# ppg.net
KiCad netlist of a schematic drawn in EAGLE
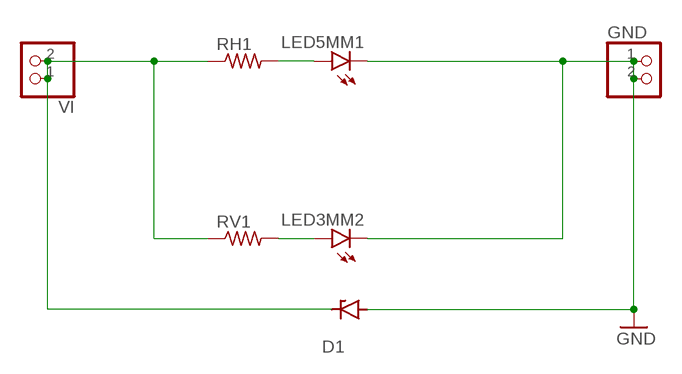
[diagram p0: schematic, sheet 1]

(export (version "E")
  (design (tool "Eeschema 10.0.6"))
  (components
    (comp (ref "D1")
      (value "ZENER-DIODEDO41Z10")
      (footprint "eagle-import:DO41Z10")
      (libsource (lib "eagle-import") (part "ZENER-DIODEDO41Z10"))
    )
    (comp (ref "GND")
      (value "PINHD-1X2")
      (footprint "eagle-import:1X02")
      (libsource (lib "eagle-import") (part "PINHD-1X2"))
    )
    (comp (ref "LED3MM2")
      (value "LED3MM")
      (footprint "eagle-import:LED3MM")
      (libsource (lib "eagle-import") (part "LED3MM"))
    )
    (comp (ref "LED5MM1")
      (value "LED5MM")
      (footprint "eagle-import:LED5MM")
      (libsource (lib "eagle-import") (part "LED5MM"))
    )
    (comp (ref "RH1")
      (value "R-US_VMTA55")
      (footprint "eagle-import:VMTA55")
      (libsource (lib "eagle-import") (part "R-US_VMTA55"))
    )
    (comp (ref "RV1")
      (value "R-US_0207/5V")
      (footprint "eagle-import:0207_5V")
      (libsource (lib "eagle-import") (part "R-US_0207/5V"))
    )
    (comp (ref "VI")
      (value "PINHD-1X2")
      (footprint "eagle-import:1X02")
      (libsource (lib "eagle-import") (part "PINHD-1X2"))
    )
  )
  (nets
    (net (code "1") (name "GND") (class "Default")
      (node (ref "D1") (pin "A") (pinfunction "A_A") (pintype "passive"))
      (node (ref "GND") (pin "1") (pinfunction "1_1") (pintype "passive"))
      (node (ref "GND") (pin "2") (pinfunction "2_2") (pintype "passive"))
      (node (ref "LED3MM2") (pin "K") (pinfunction "C_K") (pintype "passive"))
      (node (ref "LED5MM1") (pin "K") (pinfunction "C_K") (pintype "passive"))
    )
    (net (code "2") (name "Net-(D1-PadC)") (class "Default")
      (node (ref "D1") (pin "C") (pinfunction "C_C") (pintype "passive"))
      (node (ref "RH1") (pin "1") (pinfunction "1_1") (pintype "passive"))
      (node (ref "RV1") (pin "1") (pinfunction "1_1") (pintype "passive"))
      (node (ref "VI") (pin "1") (pinfunction "1_1") (pintype "passive"))
      (node (ref "VI") (pin "2") (pinfunction "2_2") (pintype "passive"))
    )
    (net (code "3") (name "Net-(LED3MM2-PadA)") (class "Default")
      (node (ref "LED3MM2") (pin "A") (pinfunction "A_A") (pintype "passive"))
      (node (ref "RV1") (pin "2") (pinfunction "2_2") (pintype "passive"))
    )
    (net (code "4") (name "Net-(LED5MM1-PadA)") (class "Default")
      (node (ref "LED5MM1") (pin "A") (pinfunction "A_A") (pintype "passive"))
      (node (ref "RH1") (pin "2") (pinfunction "2_2") (pintype "passive"))
    )
  )
)
